# ATmega32_ComServ.net
KiCad netlist of a schematic drawn in EAGLE
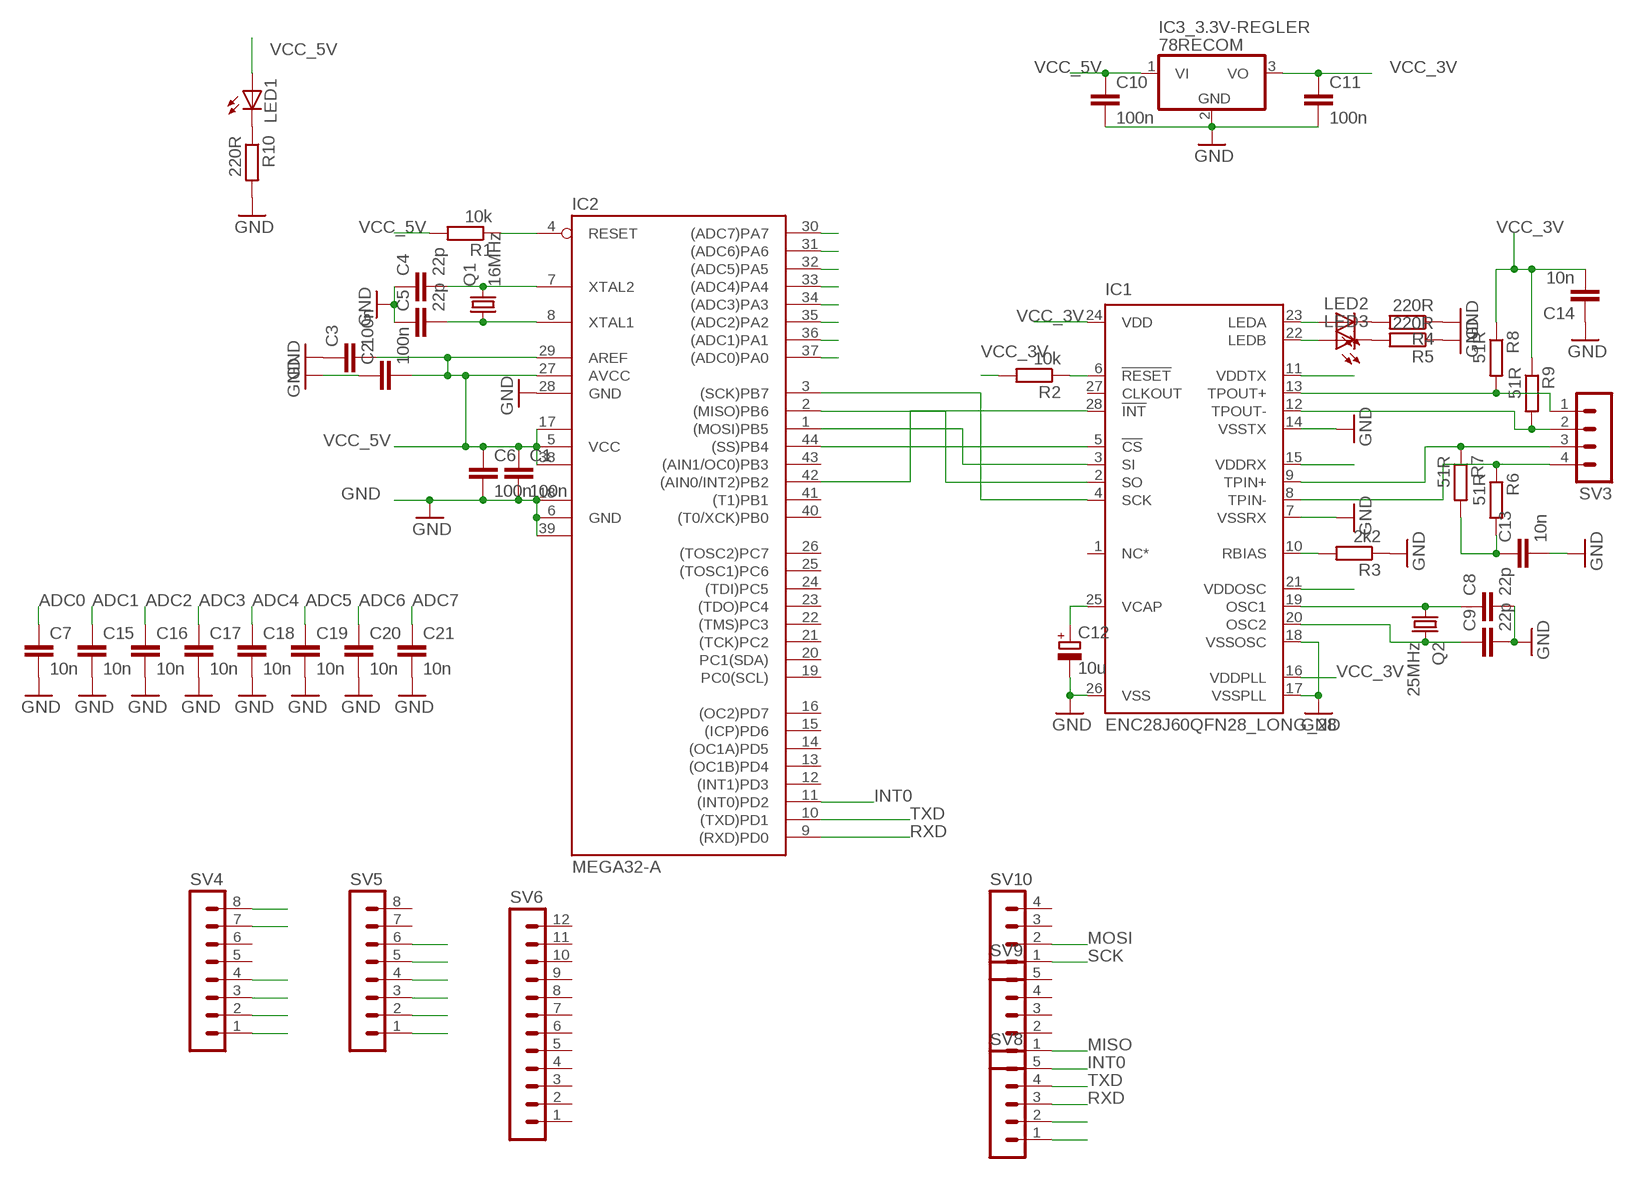
[diagram p0: schematic, sheet 1]

(export (version "E")
  (design (tool "Eeschema 10.0.6"))
  (components
    (comp (ref "C1")
      (value "100n")
      (footprint "eagle-import:C0805")
      (libsource (lib "eagle-import") (part "C-EUC0805"))
    )
    (comp (ref "C2")
      (value "100n")
      (footprint "eagle-import:C0805")
      (libsource (lib "eagle-import") (part "C-EUC0805"))
    )
    (comp (ref "C3")
      (value "100n")
      (footprint "eagle-import:C0805")
      (libsource (lib "eagle-import") (part "C-EUC0805"))
    )
    (comp (ref "C4")
      (value "22p")
      (footprint "eagle-import:C0805")
      (libsource (lib "eagle-import") (part "C-EUC0805"))
    )
    (comp (ref "C5")
      (value "22p")
      (footprint "eagle-import:C0805")
      (libsource (lib "eagle-import") (part "C-EUC0805"))
    )
    (comp (ref "C6")
      (value "100n")
      (footprint "eagle-import:C0805")
      (libsource (lib "eagle-import") (part "C-EUC0805"))
    )
    (comp (ref "C7")
      (value "10n")
      (footprint "eagle-import:C0805")
      (libsource (lib "eagle-import") (part "C-EUC0805"))
    )
    (comp (ref "C8")
      (value "22p")
      (footprint "eagle-import:C0805")
      (libsource (lib "eagle-import") (part "C-EUC0805"))
    )
    (comp (ref "C9")
      (value "22p")
      (footprint "eagle-import:C0805")
      (libsource (lib "eagle-import") (part "C-EUC0805"))
    )
    (comp (ref "C10")
      (value "100n")
      (footprint "eagle-import:C0805")
      (libsource (lib "eagle-import") (part "C-EUC0805"))
    )
    (comp (ref "C11")
      (value "100n")
      (footprint "eagle-import:C0805")
      (libsource (lib "eagle-import") (part "C-EUC0805"))
    )
    (comp (ref "C12")
      (value "10u")
      (footprint "eagle-import:SMC_D")
      (libsource (lib "eagle-import") (part "CPOL-EUSMCD"))
    )
    (comp (ref "C13")
      (value "10n")
      (footprint "eagle-import:C0805")
      (libsource (lib "eagle-import") (part "C-EUC0805"))
    )
    (comp (ref "C14")
      (value "10n")
      (footprint "eagle-import:C0805")
      (libsource (lib "eagle-import") (part "C-EUC0805"))
    )
    (comp (ref "C15")
      (value "10n")
      (footprint "eagle-import:C0805")
      (libsource (lib "eagle-import") (part "C-EUC0805"))
    )
    (comp (ref "C16")
      (value "10n")
      (footprint "eagle-import:C0805")
      (libsource (lib "eagle-import") (part "C-EUC0805"))
    )
    (comp (ref "C17")
      (value "10n")
      (footprint "eagle-import:C0805")
      (libsource (lib "eagle-import") (part "C-EUC0805"))
    )
    (comp (ref "C18")
      (value "10n")
      (footprint "eagle-import:C0805")
      (libsource (lib "eagle-import") (part "C-EUC0805"))
    )
    (comp (ref "C19")
      (value "10n")
      (footprint "eagle-import:C0805")
      (libsource (lib "eagle-import") (part "C-EUC0805"))
    )
    (comp (ref "C20")
      (value "10n")
      (footprint "eagle-import:C0805")
      (libsource (lib "eagle-import") (part "C-EUC0805"))
    )
    (comp (ref "C21")
      (value "10n")
      (footprint "eagle-import:C0805")
      (libsource (lib "eagle-import") (part "C-EUC0805"))
    )
    (comp (ref "IC1")
      (value "ENC28J60QFN28_LONG_28")
      (footprint "eagle-import:QFN28_LONG_ERRLES")
      (libsource (lib "eagle-import") (part "ENC28J60QFN28_LONG_28"))
    )
    (comp (ref "IC2")
      (value "MEGA32-A")
      (footprint "eagle-import:TQFP44")
      (libsource (lib "eagle-import") (part "MEGA32-A"))
    )
    (comp (ref "IC3_3.3V-REGLER")
      (value "78RECOM")
      (footprint "eagle-import:RECOM_3POL")
      (libsource (lib "eagle-import") (part "78RECOM"))
    )
    (comp (ref "LED1")
      (value "LEDCHIPLED_1206")
      (footprint "eagle-import:CHIPLED_1206")
      (libsource (lib "eagle-import") (part "LEDCHIPLED_1206"))
    )
    (comp (ref "LED2")
      (value "LEDCHIPLED_1206")
      (footprint "eagle-import:CHIPLED_1206")
      (libsource (lib "eagle-import") (part "LEDCHIPLED_1206"))
    )
    (comp (ref "LED3")
      (value "LEDCHIPLED_1206")
      (footprint "eagle-import:CHIPLED_1206")
      (libsource (lib "eagle-import") (part "LEDCHIPLED_1206"))
    )
    (comp (ref "Q1")
      (value "16MHz")
      (footprint "eagle-import:HC49_S")
      (libsource (lib "eagle-import") (part "CRYSTALHC49S"))
    )
    (comp (ref "Q2")
      (value "25MHz")
      (footprint "eagle-import:HC49_S")
      (libsource (lib "eagle-import") (part "CRYSTALHC49S"))
    )
    (comp (ref "R1")
      (value "10k")
      (footprint "eagle-import:R1206")
      (libsource (lib "eagle-import") (part "R-EU_R1206"))
    )
    (comp (ref "R2")
      (value "10k")
      (footprint "eagle-import:R1206")
      (libsource (lib "eagle-import") (part "R-EU_R1206"))
    )
    (comp (ref "R3")
      (value "2k2")
      (footprint "eagle-import:R1206")
      (libsource (lib "eagle-import") (part "R-EU_R1206"))
    )
    (comp (ref "R4")
      (value "220R")
      (footprint "eagle-import:R1206")
      (libsource (lib "eagle-import") (part "R-EU_R1206"))
    )
    (comp (ref "R5")
      (value "220R")
      (footprint "eagle-import:R1206")
      (libsource (lib "eagle-import") (part "R-EU_R1206"))
    )
    (comp (ref "R6")
      (value "51R")
      (footprint "eagle-import:R0805")
      (libsource (lib "eagle-import") (part "R-EU_R0805"))
    )
    (comp (ref "R7")
      (value "51R")
      (footprint "eagle-import:R1206")
      (libsource (lib "eagle-import") (part "R-EU_R1206"))
    )
    (comp (ref "R8")
      (value "51R")
      (footprint "eagle-import:R0805")
      (libsource (lib "eagle-import") (part "R-EU_R0805"))
    )
    (comp (ref "R9")
      (value "51R")
      (footprint "eagle-import:R0805")
      (libsource (lib "eagle-import") (part "R-EU_R0805"))
    )
    (comp (ref "R10")
      (value "220R")
      (footprint "eagle-import:R1206")
      (libsource (lib "eagle-import") (part "R-EU_R1206"))
    )
    (comp (ref "SV3")
      (value "MA04-1")
      (footprint "eagle-import:MA04-1")
      (libsource (lib "eagle-import") (part "MA04-1"))
    )
    (comp (ref "SV4")
      (value "MA08-1")
      (footprint "eagle-import:MA08-1")
      (libsource (lib "eagle-import") (part "MA08-1"))
    )
    (comp (ref "SV5")
      (value "MA08-1")
      (footprint "eagle-import:MA08-1")
      (libsource (lib "eagle-import") (part "MA08-1"))
    )
    (comp (ref "SV6")
      (value "MA12-1")
      (footprint "eagle-import:MA12-1")
      (libsource (lib "eagle-import") (part "MA12-1"))
    )
    (comp (ref "SV8")
      (value "MA05-1")
      (footprint "eagle-import:MA05-1")
      (libsource (lib "eagle-import") (part "MA05-1"))
    )
    (comp (ref "SV9")
      (value "MA05-1")
      (footprint "eagle-import:MA05-1")
      (libsource (lib "eagle-import") (part "MA05-1"))
    )
    (comp (ref "SV10")
      (value "MA04-1")
      (footprint "eagle-import:MA04-1")
      (libsource (lib "eagle-import") (part "MA04-1"))
    )
  )
  (nets
    (net (code "1") (name "/ADC0") (class "Default")
      (node (ref "C7") (pin "1") (pinfunction "1_1") (pintype "passive"))
      (node (ref "IC2") (pin "37") (pinfunction "(ADC0)PA0_37") (pintype "bidirectional"))
      (node (ref "SV4") (pin "1") (pinfunction "1_1") (pintype "passive"))
    )
    (net (code "2") (name "/ADC1") (class "Default")
      (node (ref "C15") (pin "1") (pinfunction "1_1") (pintype "passive"))
      (node (ref "IC2") (pin "36") (pinfunction "(ADC1)PA1_36") (pintype "bidirectional"))
      (node (ref "SV4") (pin "2") (pinfunction "2_2") (pintype "passive"))
    )
    (net (code "3") (name "/ADC2") (class "Default")
      (node (ref "C16") (pin "1") (pinfunction "1_1") (pintype "passive"))
      (node (ref "IC2") (pin "35") (pinfunction "(ADC2)PA2_35") (pintype "bidirectional"))
      (node (ref "SV4") (pin "3") (pinfunction "3_3") (pintype "passive"))
    )
    (net (code "4") (name "/ADC3") (class "Default")
      (node (ref "C17") (pin "1") (pinfunction "1_1") (pintype "passive"))
      (node (ref "IC2") (pin "34") (pinfunction "(ADC3)PA3_34") (pintype "bidirectional"))
      (node (ref "SV4") (pin "4") (pinfunction "4_4") (pintype "passive"))
    )
    (net (code "5") (name "/ADC4") (class "Default")
      (node (ref "C18") (pin "1") (pinfunction "1_1") (pintype "passive"))
      (node (ref "IC2") (pin "33") (pinfunction "(ADC4)PA4_33") (pintype "bidirectional"))
      (node (ref "SV4") (pin "7") (pinfunction "7_7") (pintype "passive"))
    )
    (net (code "6") (name "/ADC5") (class "Default")
      (node (ref "C19") (pin "1") (pinfunction "1_1") (pintype "passive"))
      (node (ref "IC2") (pin "32") (pinfunction "(ADC5)PA5_32") (pintype "bidirectional"))
      (node (ref "SV4") (pin "8") (pinfunction "8_8") (pintype "passive"))
    )
    (net (code "7") (name "/ADC6") (class "Default")
      (node (ref "C20") (pin "1") (pinfunction "1_1") (pintype "passive"))
      (node (ref "IC2") (pin "31") (pinfunction "(ADC6)PA6_31") (pintype "bidirectional"))
      (node (ref "SV8") (pin "1") (pinfunction "1_1") (pintype "passive"))
    )
    (net (code "8") (name "/ADC7") (class "Default")
      (node (ref "C21") (pin "1") (pinfunction "1_1") (pintype "passive"))
      (node (ref "IC2") (pin "30") (pinfunction "(ADC7)PA7_30") (pintype "bidirectional"))
      (node (ref "SV8") (pin "2") (pinfunction "2_2") (pintype "passive"))
    )
    (net (code "9") (name "/INT0") (class "Default")
      (node (ref "IC2") (pin "11") (pinfunction "(INT0)PD2_11") (pintype "bidirectional"))
      (node (ref "SV8") (pin "5") (pinfunction "5_5") (pintype "passive"))
    )
    (net (code "10") (name "/MISO") (class "Default")
      (node (ref "IC1") (pin "2") (pinfunction "SO_2") (pintype "output"))
      (node (ref "IC2") (pin "2") (pinfunction "(MISO)PB6_2") (pintype "bidirectional"))
      (node (ref "SV9") (pin "1") (pinfunction "1_1") (pintype "passive"))
    )
    (net (code "11") (name "/MOSI") (class "Default")
      (node (ref "IC1") (pin "3") (pinfunction "SI_3") (pintype "input"))
      (node (ref "IC2") (pin "1") (pinfunction "(MOSI)PB5_1") (pintype "bidirectional"))
      (node (ref "SV10") (pin "2") (pinfunction "2_2") (pintype "passive"))
    )
    (net (code "12") (name "/RESET") (class "Default")
      (node (ref "IC2") (pin "4") (pinfunction "RESET_4") (pintype "input"))
      (node (ref "R1") (pin "1") (pinfunction "1_1") (pintype "passive"))
      (node (ref "SV5") (pin "1") (pinfunction "1_1") (pintype "passive"))
    )
    (net (code "13") (name "/RXD") (class "Default")
      (node (ref "IC2") (pin "9") (pinfunction "(RXD)PD0_9") (pintype "bidirectional"))
      (node (ref "SV8") (pin "3") (pinfunction "3_3") (pintype "passive"))
    )
    (net (code "14") (name "/SCK") (class "Default")
      (node (ref "IC1") (pin "4") (pinfunction "SCK_4") (pintype "input"))
      (node (ref "IC2") (pin "3") (pinfunction "(SCK)PB7_3") (pintype "bidirectional"))
      (node (ref "SV10") (pin "1") (pinfunction "1_1") (pintype "passive"))
    )
    (net (code "15") (name "/TXD") (class "Default")
      (node (ref "IC2") (pin "10") (pinfunction "(TXD)PD1_10") (pintype "bidirectional"))
      (node (ref "SV8") (pin "4") (pinfunction "4_4") (pintype "passive"))
    )
    (net (code "16") (name "/VCC_3V") (class "Default")
      (node (ref "C11") (pin "1") (pinfunction "1_1") (pintype "passive"))
      (node (ref "C14") (pin "2") (pinfunction "2_2") (pintype "passive"))
      (node (ref "IC1") (pin "11") (pinfunction "VDDTX_11") (pintype "input"))
      (node (ref "IC1") (pin "15") (pinfunction "VDDRX_15") (pintype "input"))
      (node (ref "IC1") (pin "16") (pinfunction "VDDPLL_16") (pintype "input"))
      (node (ref "IC1") (pin "21") (pinfunction "VDDOSC_21") (pintype "input"))
      (node (ref "IC1") (pin "24") (pinfunction "VDD_24") (pintype "input"))
      (node (ref "IC3_3.3V-REGLER") (pin "3") (pinfunction "VO_3") (pintype "passive"))
      (node (ref "R2") (pin "2") (pinfunction "2_2") (pintype "passive"))
      (node (ref "R8") (pin "1") (pinfunction "1_1") (pintype "passive"))
      (node (ref "R9") (pin "1") (pinfunction "1_1") (pintype "passive"))
    )
    (net (code "17") (name "/VCC_5V") (class "Default")
      (node (ref "C1") (pin "1") (pinfunction "1_1") (pintype "passive"))
      (node (ref "C10") (pin "1") (pinfunction "1_1") (pintype "passive"))
      (node (ref "C2") (pin "2") (pinfunction "2_2") (pintype "passive"))
      (node (ref "C3") (pin "2") (pinfunction "2_2") (pintype "passive"))
      (node (ref "C6") (pin "1") (pinfunction "1_1") (pintype "passive"))
      (node (ref "IC2") (pin "17") (pinfunction "VCC1_17") (pintype "power_in"))
      (node (ref "IC2") (pin "27") (pinfunction "AVCC_27") (pintype "power_in"))
      (node (ref "IC2") (pin "29") (pinfunction "AREF_29") (pintype "passive"))
      (node (ref "IC2") (pin "38") (pinfunction "VCC2_38") (pintype "power_in"))
      (node (ref "IC2") (pin "5") (pinfunction "VCC_5") (pintype "power_in"))
      (node (ref "IC3_3.3V-REGLER") (pin "1") (pinfunction "VI_1") (pintype "input"))
      (node (ref "LED1") (pin "A") (pinfunction "A_A") (pintype "passive"))
      (node (ref "R1") (pin "2") (pinfunction "2_2") (pintype "passive"))
      (node (ref "SV5") (pin "4") (pinfunction "4_4") (pintype "passive"))
      (node (ref "SV5") (pin "5") (pinfunction "5_5") (pintype "passive"))
    )
    (net (code "18") (name "GND") (class "Default")
      (node (ref "C1") (pin "2") (pinfunction "2_2") (pintype "passive"))
      (node (ref "C10") (pin "2") (pinfunction "2_2") (pintype "passive"))
      (node (ref "C11") (pin "2") (pinfunction "2_2") (pintype "passive"))
      (node (ref "C12") (pin "-") (pinfunction "-_-") (pintype "passive"))
      (node (ref "C13") (pin "2") (pinfunction "2_2") (pintype "passive"))
      (node (ref "C14") (pin "1") (pinfunction "1_1") (pintype "passive"))
      (node (ref "C15") (pin "2") (pinfunction "2_2") (pintype "passive"))
      (node (ref "C16") (pin "2") (pinfunction "2_2") (pintype "passive"))
      (node (ref "C17") (pin "2") (pinfunction "2_2") (pintype "passive"))
      (node (ref "C18") (pin "2") (pinfunction "2_2") (pintype "passive"))
      (node (ref "C19") (pin "2") (pinfunction "2_2") (pintype "passive"))
      (node (ref "C2") (pin "1") (pinfunction "1_1") (pintype "passive"))
      (node (ref "C20") (pin "2") (pinfunction "2_2") (pintype "passive"))
      (node (ref "C21") (pin "2") (pinfunction "2_2") (pintype "passive"))
      (node (ref "C3") (pin "1") (pinfunction "1_1") (pintype "passive"))
      (node (ref "C4") (pin "1") (pinfunction "1_1") (pintype "passive"))
      (node (ref "C5") (pin "1") (pinfunction "1_1") (pintype "passive"))
      (node (ref "C6") (pin "2") (pinfunction "2_2") (pintype "passive"))
      (node (ref "C7") (pin "2") (pinfunction "2_2") (pintype "passive"))
      (node (ref "C8") (pin "2") (pinfunction "2_2") (pintype "passive"))
      (node (ref "C9") (pin "2") (pinfunction "2_2") (pintype "passive"))
      (node (ref "IC1") (pin "14") (pinfunction "VSSTX_14") (pintype "input"))
      (node (ref "IC1") (pin "17") (pinfunction "VSSPLL_17") (pintype "input"))
      (node (ref "IC1") (pin "18") (pinfunction "VSSOSC_18") (pintype "input"))
      (node (ref "IC1") (pin "26") (pinfunction "VSS_26") (pintype "input"))
      (node (ref "IC1") (pin "7") (pinfunction "VSSRX_7") (pintype "input"))
      (node (ref "IC2") (pin "18") (pinfunction "GND1_18") (pintype "power_in"))
      (node (ref "IC2") (pin "28") (pinfunction "GND_28") (pintype "power_in"))
      (node (ref "IC2") (pin "39") (pinfunction "GND2_39") (pintype "power_in"))
      (node (ref "IC2") (pin "6") (pinfunction "GND_6") (pintype "power_in"))
      (node (ref "IC3_3.3V-REGLER") (pin "2") (pinfunction "GND_2") (pintype "passive"))
      (node (ref "R10") (pin "2") (pinfunction "2_2") (pintype "passive"))
      (node (ref "R3") (pin "1") (pinfunction "1_1") (pintype "passive"))
      (node (ref "R4") (pin "1") (pinfunction "1_1") (pintype "passive"))
      (node (ref "R5") (pin "1") (pinfunction "1_1") (pintype "passive"))
      (node (ref "SV5") (pin "2") (pinfunction "2_2") (pintype "passive"))
      (node (ref "SV5") (pin "3") (pinfunction "3_3") (pintype "passive"))
      (node (ref "SV5") (pin "6") (pinfunction "6_6") (pintype "passive"))
    )
    (net (code "19") (name "Net-(C13-Pad1)") (class "Default")
      (node (ref "C13") (pin "1") (pinfunction "1_1") (pintype "passive"))
      (node (ref "R6") (pin "2") (pinfunction "2_2") (pintype "passive"))
      (node (ref "R7") (pin "2") (pinfunction "2_2") (pintype "passive"))
    )
    (net (code "20") (name "Net-(IC1-LEDA)") (class "Default")
      (node (ref "IC1") (pin "23") (pinfunction "LEDA_23") (pintype "output"))
      (node (ref "LED2") (pin "A") (pinfunction "A_A") (pintype "passive"))
    )
    (net (code "21") (name "Net-(IC1-LEDB)") (class "Default")
      (node (ref "IC1") (pin "22") (pinfunction "LEDB_22") (pintype "output"))
      (node (ref "LED3") (pin "A") (pinfunction "A_A") (pintype "passive"))
    )
    (net (code "22") (name "Net-(IC1-OSC1)") (class "Default")
      (node (ref "C8") (pin "1") (pinfunction "1_1") (pintype "passive"))
      (node (ref "IC1") (pin "19") (pinfunction "OSC1_19") (pintype "input"))
      (node (ref "Q2") (pin "1") (pinfunction "1_1") (pintype "passive"))
    )
    (net (code "23") (name "Net-(IC1-OSC2)") (class "Default")
      (node (ref "C9") (pin "1") (pinfunction "1_1") (pintype "passive"))
      (node (ref "IC1") (pin "20") (pinfunction "OSC2_20") (pintype "output"))
      (node (ref "Q2") (pin "2") (pinfunction "2_2") (pintype "passive"))
    )
    (net (code "24") (name "Net-(IC1-RBIAS)") (class "Default")
      (node (ref "IC1") (pin "10") (pinfunction "RBIAS_10") (pintype "input"))
      (node (ref "R3") (pin "2") (pinfunction "2_2") (pintype "passive"))
    )
    (net (code "25") (name "Net-(IC1-TPIN+)") (class "Default")
      (node (ref "IC1") (pin "9") (pinfunction "TPIN+_9") (pintype "input"))
      (node (ref "R7") (pin "1") (pinfunction "1_1") (pintype "passive"))
      (node (ref "SV3") (pin "3") (pinfunction "3_3") (pintype "passive"))
    )
    (net (code "26") (name "Net-(IC1-TPIN-)") (class "Default")
      (node (ref "IC1") (pin "8") (pinfunction "TPIN-_8") (pintype "input"))
      (node (ref "R6") (pin "1") (pinfunction "1_1") (pintype "passive"))
      (node (ref "SV3") (pin "4") (pinfunction "4_4") (pintype "passive"))
    )
    (net (code "27") (name "Net-(IC1-TPOUT+)") (class "Default")
      (node (ref "IC1") (pin "13") (pinfunction "TPOUT+_13") (pintype "output"))
      (node (ref "R8") (pin "2") (pinfunction "2_2") (pintype "passive"))
      (node (ref "SV3") (pin "1") (pinfunction "1_1") (pintype "passive"))
    )
    (net (code "28") (name "Net-(IC1-TPOUT-)") (class "Default")
      (node (ref "IC1") (pin "12") (pinfunction "TPOUT-_12") (pintype "output"))
      (node (ref "R9") (pin "2") (pinfunction "2_2") (pintype "passive"))
      (node (ref "SV3") (pin "2") (pinfunction "2_2") (pintype "passive"))
    )
    (net (code "29") (name "Net-(IC1-VCAP)") (class "Default")
      (node (ref "C12") (pin "+") (pinfunction "+_+") (pintype "passive"))
      (node (ref "IC1") (pin "25") (pinfunction "VCAP_25") (pintype "input"))
    )
    (net (code "30") (name "Net-(IC1-~{CS})") (class "Default")
      (node (ref "IC1") (pin "5") (pinfunction "~{CS}_5") (pintype "input"))
      (node (ref "IC2") (pin "44") (pinfunction "(SS)PB4_44") (pintype "bidirectional"))
    )
    (net (code "31") (name "Net-(IC1-~{INT})") (class "Default")
      (node (ref "IC1") (pin "28") (pinfunction "~{INT}_28") (pintype "output"))
      (node (ref "IC2") (pin "42") (pinfunction "(AIN0/INT2)PB2_42") (pintype "bidirectional"))
    )
    (net (code "32") (name "Net-(IC1-~{RESET})") (class "Default")
      (node (ref "IC1") (pin "6") (pinfunction "~{RESET}_6") (pintype "input"))
      (node (ref "R2") (pin "1") (pinfunction "1_1") (pintype "passive"))
    )
    (net (code "33") (name "Net-(IC2-XTAL1)") (class "Default")
      (node (ref "C5") (pin "2") (pinfunction "2_2") (pintype "passive"))
      (node (ref "IC2") (pin "8") (pinfunction "XTAL1_8") (pintype "bidirectional"))
      (node (ref "Q1") (pin "1") (pinfunction "1_1") (pintype "passive"))
    )
    (net (code "34") (name "Net-(IC2-XTAL2)") (class "Default")
      (node (ref "C4") (pin "2") (pinfunction "2_2") (pintype "passive"))
      (node (ref "IC2") (pin "7") (pinfunction "XTAL2_7") (pintype "bidirectional"))
      (node (ref "Q1") (pin "2") (pinfunction "2_2") (pintype "passive"))
    )
    (net (code "35") (name "Net-(LED1-PadC)") (class "Default")
      (node (ref "LED1") (pin "C") (pinfunction "C_C") (pintype "passive"))
      (node (ref "R10") (pin "1") (pinfunction "1_1") (pintype "passive"))
    )
    (net (code "36") (name "Net-(LED2-PadC)") (class "Default")
      (node (ref "LED2") (pin "C") (pinfunction "C_C") (pintype "passive"))
      (node (ref "R4") (pin "2") (pinfunction "2_2") (pintype "passive"))
    )
    (net (code "37") (name "Net-(LED3-PadC)") (class "Default")
      (node (ref "LED3") (pin "C") (pinfunction "C_C") (pintype "passive"))
      (node (ref "R5") (pin "2") (pinfunction "2_2") (pintype "passive"))
    )
    (net (code "38") (name "unconnected-(IC1-CLKOUT-Pad27)") (class "Default")
      (node (ref "IC1") (pin "27") (pinfunction "CLKOUT_27") (pintype "output"))
    )
    (net (code "39") (name "unconnected-(IC1-NC*-Pad1)") (class "Default")
      (node (ref "IC1") (pin "1") (pinfunction "NC*_1") (pintype "output"))
    )
    (net (code "40") (name "unconnected-(IC2-(AIN1{slash}OC0)PB3-Pad43)") (class "Default")
      (node (ref "IC2") (pin "43") (pinfunction "(AIN1/OC0)PB3_43") (pintype "bidirectional"))
    )
    (net (code "41") (name "unconnected-(IC2-(ICP)PD6-Pad15)") (class "Default")
      (node (ref "IC2") (pin "15") (pinfunction "(ICP)PD6_15") (pintype "bidirectional"))
    )
    (net (code "42") (name "unconnected-(IC2-(INT1)PD3-Pad12)") (class "Default")
      (node (ref "IC2") (pin "12") (pinfunction "(INT1)PD3_12") (pintype "bidirectional"))
    )
    (net (code "43") (name "unconnected-(IC2-(OC1A)PD5-Pad14)") (class "Default")
      (node (ref "IC2") (pin "14") (pinfunction "(OC1A)PD5_14") (pintype "bidirectional"))
    )
    (net (code "44") (name "unconnected-(IC2-(OC1B)PD4-Pad13)") (class "Default")
      (node (ref "IC2") (pin "13") (pinfunction "(OC1B)PD4_13") (pintype "bidirectional"))
    )
    (net (code "45") (name "unconnected-(IC2-(OC2)PD7-Pad16)") (class "Default")
      (node (ref "IC2") (pin "16") (pinfunction "(OC2)PD7_16") (pintype "bidirectional"))
    )
    (net (code "46") (name "unconnected-(IC2-(T0{slash}XCK)PB0-Pad40)") (class "Default")
      (node (ref "IC2") (pin "40") (pinfunction "(T0/XCK)PB0_40") (pintype "bidirectional"))
    )
    (net (code "47") (name "unconnected-(IC2-(T1)PB1-Pad41)") (class "Default")
      (node (ref "IC2") (pin "41") (pinfunction "(T1)PB1_41") (pintype "bidirectional"))
    )
    (net (code "48") (name "unconnected-(IC2-(TCK)PC2-Pad21)") (class "Default")
      (node (ref "IC2") (pin "21") (pinfunction "(TCK)PC2_21") (pintype "bidirectional"))
    )
    (net (code "49") (name "unconnected-(IC2-(TDI)PC5-Pad24)") (class "Default")
      (node (ref "IC2") (pin "24") (pinfunction "(TDI)PC5_24") (pintype "bidirectional"))
    )
    (net (code "50") (name "unconnected-(IC2-(TDO)PC4-Pad23)") (class "Default")
      (node (ref "IC2") (pin "23") (pinfunction "(TDO)PC4_23") (pintype "bidirectional"))
    )
    (net (code "51") (name "unconnected-(IC2-(TMS)PC3-Pad22)") (class "Default")
      (node (ref "IC2") (pin "22") (pinfunction "(TMS)PC3_22") (pintype "bidirectional"))
    )
    (net (code "52") (name "unconnected-(IC2-(TOSC1)PC6-Pad25)") (class "Default")
      (node (ref "IC2") (pin "25") (pinfunction "(TOSC1)PC6_25") (pintype "bidirectional"))
    )
    (net (code "53") (name "unconnected-(IC2-(TOSC2)PC7-Pad26)") (class "Default")
      (node (ref "IC2") (pin "26") (pinfunction "(TOSC2)PC7_26") (pintype "bidirectional"))
    )
    (net (code "54") (name "unconnected-(IC2-PC0(SCL)-Pad19)") (class "Default")
      (node (ref "IC2") (pin "19") (pinfunction "PC0(SCL)_19") (pintype "bidirectional"))
    )
    (net (code "55") (name "unconnected-(IC2-PC1(SDA)-Pad20)") (class "Default")
      (node (ref "IC2") (pin "20") (pinfunction "PC1(SDA)_20") (pintype "bidirectional"))
    )
    (net (code "56") (name "unconnected-(SV4-Pad5)") (class "Default")
      (node (ref "SV4") (pin "5") (pinfunction "5_5") (pintype "passive"))
    )
    (net (code "57") (name "unconnected-(SV4-Pad6)") (class "Default")
      (node (ref "SV4") (pin "6") (pinfunction "6_6") (pintype "passive"))
    )
    (net (code "58") (name "unconnected-(SV5-Pad7)") (class "Default")
      (node (ref "SV5") (pin "7") (pinfunction "7_7") (pintype "passive"))
    )
    (net (code "59") (name "unconnected-(SV5-Pad8)") (class "Default")
      (node (ref "SV5") (pin "8") (pinfunction "8_8") (pintype "passive"))
    )
    (net (code "60") (name "unconnected-(SV6-Pad1)") (class "Default")
      (node (ref "SV6") (pin "1") (pinfunction "1_1") (pintype "passive"))
    )
    (net (code "61") (name "unconnected-(SV6-Pad2)") (class "Default")
      (node (ref "SV6") (pin "2") (pinfunction "2_2") (pintype "passive"))
    )
    (net (code "62") (name "unconnected-(SV6-Pad3)") (class "Default")
      (node (ref "SV6") (pin "3") (pinfunction "3_3") (pintype "passive"))
    )
    (net (code "63") (name "unconnected-(SV6-Pad4)") (class "Default")
      (node (ref "SV6") (pin "4") (pinfunction "4_4") (pintype "passive"))
    )
    (net (code "64") (name "unconnected-(SV6-Pad5)") (class "Default")
      (node (ref "SV6") (pin "5") (pinfunction "5_5") (pintype "passive"))
    )
    (net (code "65") (name "unconnected-(SV6-Pad6)") (class "Default")
      (node (ref "SV6") (pin "6") (pinfunction "6_6") (pintype "passive"))
    )
    (net (code "66") (name "unconnected-(SV6-Pad7)") (class "Default")
      (node (ref "SV6") (pin "7") (pinfunction "7_7") (pintype "passive"))
    )
    (net (code "67") (name "unconnected-(SV6-Pad8)") (class "Default")
      (node (ref "SV6") (pin "8") (pinfunction "8_8") (pintype "passive"))
    )
    (net (code "68") (name "unconnected-(SV6-Pad9)") (class "Default")
      (node (ref "SV6") (pin "9") (pinfunction "9_9") (pintype "passive"))
    )
    (net (code "69") (name "unconnected-(SV6-Pad10)") (class "Default")
      (node (ref "SV6") (pin "10") (pinfunction "10_10") (pintype "passive"))
    )
    (net (code "70") (name "unconnected-(SV6-Pad11)") (class "Default")
      (node (ref "SV6") (pin "11") (pinfunction "11_11") (pintype "passive"))
    )
    (net (code "71") (name "unconnected-(SV6-Pad12)") (class "Default")
      (node (ref "SV6") (pin "12") (pinfunction "12_12") (pintype "passive"))
    )
    (net (code "72") (name "unconnected-(SV9-Pad2)") (class "Default")
      (node (ref "SV9") (pin "2") (pinfunction "2_2") (pintype "passive"))
    )
    (net (code "73") (name "unconnected-(SV9-Pad3)") (class "Default")
      (node (ref "SV9") (pin "3") (pinfunction "3_3") (pintype "passive"))
    )
    (net (code "74") (name "unconnected-(SV9-Pad4)") (class "Default")
      (node (ref "SV9") (pin "4") (pinfunction "4_4") (pintype "passive"))
    )
    (net (code "75") (name "unconnected-(SV9-Pad5)") (class "Default")
      (node (ref "SV9") (pin "5") (pinfunction "5_5") (pintype "passive"))
    )
    (net (code "76") (name "unconnected-(SV10-Pad3)") (class "Default")
      (node (ref "SV10") (pin "3") (pinfunction "3_3") (pintype "passive"))
    )
    (net (code "77") (name "unconnected-(SV10-Pad4)") (class "Default")
      (node (ref "SV10") (pin "4") (pinfunction "4_4") (pintype "passive"))
    )
  )
)
